# DSPCONN2.net
KiCad netlist of a schematic drawn in Altium Designer
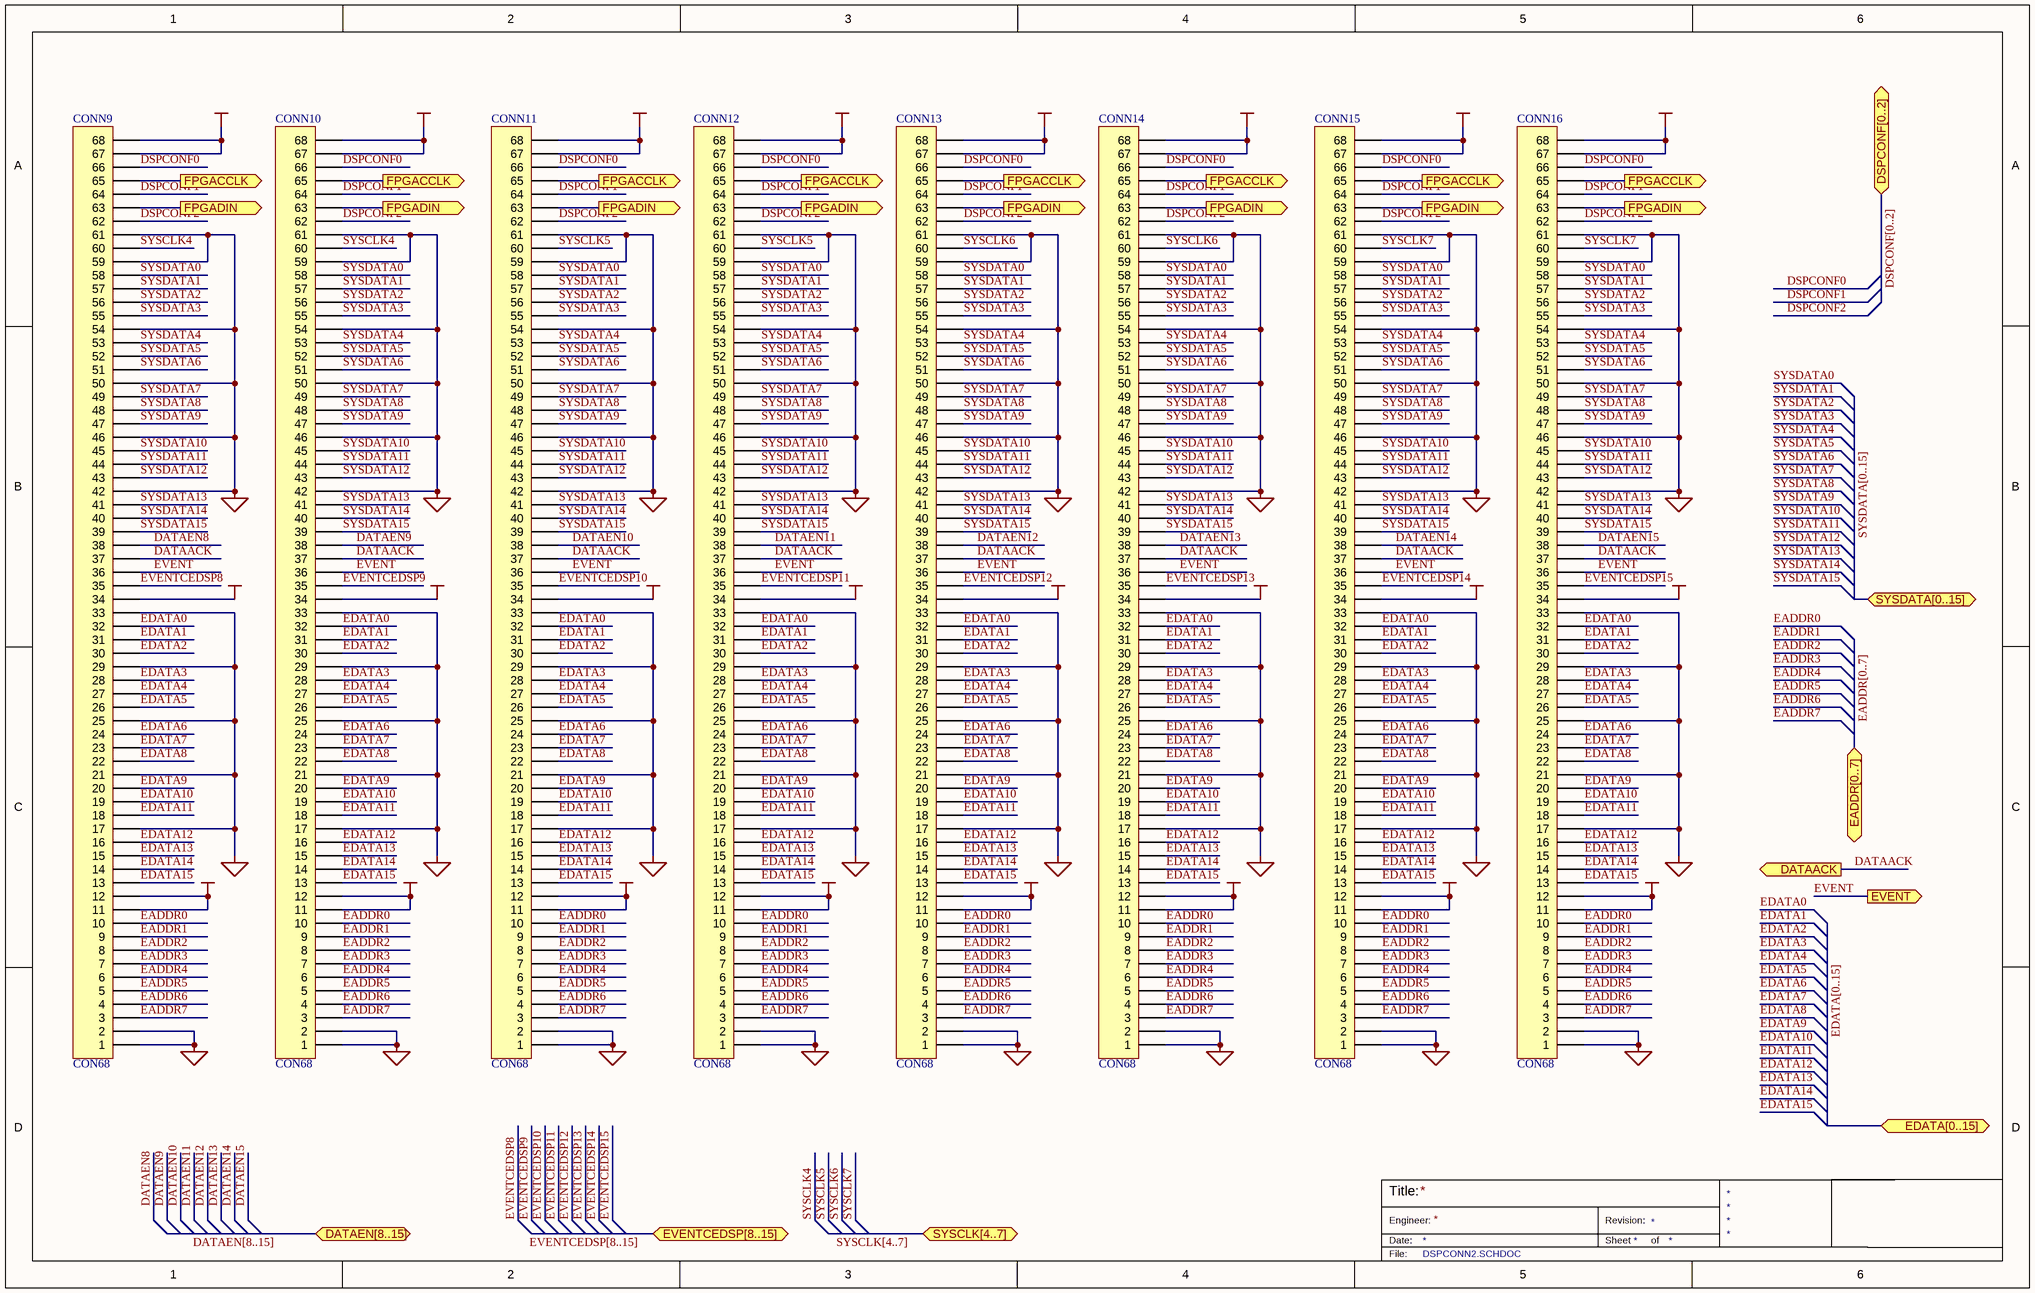
[diagram p0: DSPCONN2.SCHDOC]

(export (version "E")
  (design (tool "Eeschema 10.0.6"))
  (components
    (comp (ref "CONN9")
      (value "CON68")
      (footprint "MOLEX 15921068")
      (libsource (lib "My devices") (part "CON68"))
    )
    (comp (ref "CONN10")
      (value "CON68")
      (footprint "MOLEX 15921068")
      (libsource (lib "My devices") (part "CON68"))
    )
    (comp (ref "CONN11")
      (value "CON68")
      (footprint "MOLEX 15921068")
      (libsource (lib "My devices") (part "CON68"))
    )
    (comp (ref "CONN12")
      (value "CON68")
      (footprint "MOLEX 15921068")
      (libsource (lib "My devices") (part "CON68"))
    )
    (comp (ref "CONN13")
      (value "CON68")
      (footprint "MOLEX 15921068")
      (libsource (lib "My devices") (part "CON68"))
    )
    (comp (ref "CONN14")
      (value "CON68")
      (footprint "MOLEX 15921068")
      (libsource (lib "My devices") (part "CON68"))
    )
    (comp (ref "CONN15")
      (value "CON68")
      (footprint "MOLEX 15921068")
      (libsource (lib "My devices") (part "CON68"))
    )
    (comp (ref "CONN16")
      (value "CON68")
      (footprint "MOLEX 15921068")
      (libsource (lib "My devices") (part "CON68"))
    )
  )
  (nets
    (net (code "1") (name "+5VCC") (class "Default")
      (node (ref "CONN10") (pin "34") (pinfunction "34_34") (pintype "passive"))
      (node (ref "CONN11") (pin "34") (pinfunction "34_34") (pintype "passive"))
      (node (ref "CONN12") (pin "34") (pinfunction "34_34") (pintype "passive"))
      (node (ref "CONN13") (pin "34") (pinfunction "34_34") (pintype "passive"))
      (node (ref "CONN14") (pin "34") (pinfunction "34_34") (pintype "passive"))
      (node (ref "CONN15") (pin "34") (pinfunction "34_34") (pintype "passive"))
      (node (ref "CONN16") (pin "34") (pinfunction "34_34") (pintype "passive"))
      (node (ref "CONN9") (pin "34") (pinfunction "34_34") (pintype "passive"))
    )
    (net (code "2") (name "/DATAACK") (class "Default")
      (node (ref "CONN10") (pin "37") (pinfunction "37_37") (pintype "passive"))
      (node (ref "CONN11") (pin "37") (pinfunction "37_37") (pintype "passive"))
      (node (ref "CONN12") (pin "37") (pinfunction "37_37") (pintype "passive"))
      (node (ref "CONN13") (pin "37") (pinfunction "37_37") (pintype "passive"))
      (node (ref "CONN14") (pin "37") (pinfunction "37_37") (pintype "passive"))
      (node (ref "CONN15") (pin "37") (pinfunction "37_37") (pintype "passive"))
      (node (ref "CONN16") (pin "37") (pinfunction "37_37") (pintype "passive"))
      (node (ref "CONN9") (pin "37") (pinfunction "37_37") (pintype "passive"))
    )
    (net (code "3") (name "/DATAEN8") (class "Default")
      (node (ref "CONN9") (pin "38") (pinfunction "38_38") (pintype "passive"))
    )
    (net (code "4") (name "/DATAEN9") (class "Default")
      (node (ref "CONN10") (pin "38") (pinfunction "38_38") (pintype "passive"))
    )
    (net (code "5") (name "/DATAEN10") (class "Default")
      (node (ref "CONN11") (pin "38") (pinfunction "38_38") (pintype "passive"))
    )
    (net (code "6") (name "/DATAEN11") (class "Default")
      (node (ref "CONN12") (pin "38") (pinfunction "38_38") (pintype "passive"))
    )
    (net (code "7") (name "/DATAEN12") (class "Default")
      (node (ref "CONN13") (pin "38") (pinfunction "38_38") (pintype "passive"))
    )
    (net (code "8") (name "/DATAEN13") (class "Default")
      (node (ref "CONN14") (pin "38") (pinfunction "38_38") (pintype "passive"))
    )
    (net (code "9") (name "/DATAEN14") (class "Default")
      (node (ref "CONN15") (pin "38") (pinfunction "38_38") (pintype "passive"))
    )
    (net (code "10") (name "/DATAEN15") (class "Default")
      (node (ref "CONN16") (pin "38") (pinfunction "38_38") (pintype "passive"))
    )
    (net (code "12") (name "/DSPCONF0") (class "Default")
      (node (ref "CONN10") (pin "66") (pinfunction "66_66") (pintype "passive"))
      (node (ref "CONN11") (pin "66") (pinfunction "66_66") (pintype "passive"))
      (node (ref "CONN12") (pin "66") (pinfunction "66_66") (pintype "passive"))
      (node (ref "CONN13") (pin "66") (pinfunction "66_66") (pintype "passive"))
      (node (ref "CONN14") (pin "66") (pinfunction "66_66") (pintype "passive"))
      (node (ref "CONN15") (pin "66") (pinfunction "66_66") (pintype "passive"))
      (node (ref "CONN16") (pin "66") (pinfunction "66_66") (pintype "passive"))
      (node (ref "CONN9") (pin "66") (pinfunction "66_66") (pintype "passive"))
    )
    (net (code "13") (name "/DSPCONF1") (class "Default")
      (node (ref "CONN10") (pin "64") (pinfunction "64_64") (pintype "passive"))
      (node (ref "CONN11") (pin "64") (pinfunction "64_64") (pintype "passive"))
      (node (ref "CONN12") (pin "64") (pinfunction "64_64") (pintype "passive"))
      (node (ref "CONN13") (pin "64") (pinfunction "64_64") (pintype "passive"))
      (node (ref "CONN14") (pin "64") (pinfunction "64_64") (pintype "passive"))
      (node (ref "CONN15") (pin "64") (pinfunction "64_64") (pintype "passive"))
      (node (ref "CONN16") (pin "64") (pinfunction "64_64") (pintype "passive"))
      (node (ref "CONN9") (pin "64") (pinfunction "64_64") (pintype "passive"))
    )
    (net (code "14") (name "/DSPCONF2") (class "Default")
      (node (ref "CONN10") (pin "62") (pinfunction "62_62") (pintype "passive"))
      (node (ref "CONN11") (pin "62") (pinfunction "62_62") (pintype "passive"))
      (node (ref "CONN12") (pin "62") (pinfunction "62_62") (pintype "passive"))
      (node (ref "CONN13") (pin "62") (pinfunction "62_62") (pintype "passive"))
      (node (ref "CONN14") (pin "62") (pinfunction "62_62") (pintype "passive"))
      (node (ref "CONN15") (pin "62") (pinfunction "62_62") (pintype "passive"))
      (node (ref "CONN16") (pin "62") (pinfunction "62_62") (pintype "passive"))
      (node (ref "CONN9") (pin "62") (pinfunction "62_62") (pintype "passive"))
    )
    (net (code "16") (name "/EADDR0") (class "Default")
      (node (ref "CONN10") (pin "10") (pinfunction "10_10") (pintype "passive"))
      (node (ref "CONN11") (pin "10") (pinfunction "10_10") (pintype "passive"))
      (node (ref "CONN12") (pin "10") (pinfunction "10_10") (pintype "passive"))
      (node (ref "CONN13") (pin "10") (pinfunction "10_10") (pintype "passive"))
      (node (ref "CONN14") (pin "10") (pinfunction "10_10") (pintype "passive"))
      (node (ref "CONN15") (pin "10") (pinfunction "10_10") (pintype "passive"))
      (node (ref "CONN16") (pin "10") (pinfunction "10_10") (pintype "passive"))
      (node (ref "CONN9") (pin "10") (pinfunction "10_10") (pintype "passive"))
    )
    (net (code "17") (name "/EADDR1") (class "Default")
      (node (ref "CONN10") (pin "9") (pinfunction "9_9") (pintype "passive"))
      (node (ref "CONN11") (pin "9") (pinfunction "9_9") (pintype "passive"))
      (node (ref "CONN12") (pin "9") (pinfunction "9_9") (pintype "passive"))
      (node (ref "CONN13") (pin "9") (pinfunction "9_9") (pintype "passive"))
      (node (ref "CONN14") (pin "9") (pinfunction "9_9") (pintype "passive"))
      (node (ref "CONN15") (pin "9") (pinfunction "9_9") (pintype "passive"))
      (node (ref "CONN16") (pin "9") (pinfunction "9_9") (pintype "passive"))
      (node (ref "CONN9") (pin "9") (pinfunction "9_9") (pintype "passive"))
    )
    (net (code "18") (name "/EADDR2") (class "Default")
      (node (ref "CONN10") (pin "8") (pinfunction "8_8") (pintype "passive"))
      (node (ref "CONN11") (pin "8") (pinfunction "8_8") (pintype "passive"))
      (node (ref "CONN12") (pin "8") (pinfunction "8_8") (pintype "passive"))
      (node (ref "CONN13") (pin "8") (pinfunction "8_8") (pintype "passive"))
      (node (ref "CONN14") (pin "8") (pinfunction "8_8") (pintype "passive"))
      (node (ref "CONN15") (pin "8") (pinfunction "8_8") (pintype "passive"))
      (node (ref "CONN16") (pin "8") (pinfunction "8_8") (pintype "passive"))
      (node (ref "CONN9") (pin "8") (pinfunction "8_8") (pintype "passive"))
    )
    (net (code "19") (name "/EADDR3") (class "Default")
      (node (ref "CONN10") (pin "7") (pinfunction "7_7") (pintype "passive"))
      (node (ref "CONN11") (pin "7") (pinfunction "7_7") (pintype "passive"))
      (node (ref "CONN12") (pin "7") (pinfunction "7_7") (pintype "passive"))
      (node (ref "CONN13") (pin "7") (pinfunction "7_7") (pintype "passive"))
      (node (ref "CONN14") (pin "7") (pinfunction "7_7") (pintype "passive"))
      (node (ref "CONN15") (pin "7") (pinfunction "7_7") (pintype "passive"))
      (node (ref "CONN16") (pin "7") (pinfunction "7_7") (pintype "passive"))
      (node (ref "CONN9") (pin "7") (pinfunction "7_7") (pintype "passive"))
    )
    (net (code "20") (name "/EADDR4") (class "Default")
      (node (ref "CONN10") (pin "6") (pinfunction "6_6") (pintype "passive"))
      (node (ref "CONN11") (pin "6") (pinfunction "6_6") (pintype "passive"))
      (node (ref "CONN12") (pin "6") (pinfunction "6_6") (pintype "passive"))
      (node (ref "CONN13") (pin "6") (pinfunction "6_6") (pintype "passive"))
      (node (ref "CONN14") (pin "6") (pinfunction "6_6") (pintype "passive"))
      (node (ref "CONN15") (pin "6") (pinfunction "6_6") (pintype "passive"))
      (node (ref "CONN16") (pin "6") (pinfunction "6_6") (pintype "passive"))
      (node (ref "CONN9") (pin "6") (pinfunction "6_6") (pintype "passive"))
    )
    (net (code "21") (name "/EADDR5") (class "Default")
      (node (ref "CONN10") (pin "5") (pinfunction "5_5") (pintype "passive"))
      (node (ref "CONN11") (pin "5") (pinfunction "5_5") (pintype "passive"))
      (node (ref "CONN12") (pin "5") (pinfunction "5_5") (pintype "passive"))
      (node (ref "CONN13") (pin "5") (pinfunction "5_5") (pintype "passive"))
      (node (ref "CONN14") (pin "5") (pinfunction "5_5") (pintype "passive"))
      (node (ref "CONN15") (pin "5") (pinfunction "5_5") (pintype "passive"))
      (node (ref "CONN16") (pin "5") (pinfunction "5_5") (pintype "passive"))
      (node (ref "CONN9") (pin "5") (pinfunction "5_5") (pintype "passive"))
    )
    (net (code "22") (name "/EADDR6") (class "Default")
      (node (ref "CONN10") (pin "4") (pinfunction "4_4") (pintype "passive"))
      (node (ref "CONN11") (pin "4") (pinfunction "4_4") (pintype "passive"))
      (node (ref "CONN12") (pin "4") (pinfunction "4_4") (pintype "passive"))
      (node (ref "CONN13") (pin "4") (pinfunction "4_4") (pintype "passive"))
      (node (ref "CONN14") (pin "4") (pinfunction "4_4") (pintype "passive"))
      (node (ref "CONN15") (pin "4") (pinfunction "4_4") (pintype "passive"))
      (node (ref "CONN16") (pin "4") (pinfunction "4_4") (pintype "passive"))
      (node (ref "CONN9") (pin "4") (pinfunction "4_4") (pintype "passive"))
    )
    (net (code "23") (name "/EADDR7") (class "Default")
      (node (ref "CONN10") (pin "3") (pinfunction "3_3") (pintype "passive"))
      (node (ref "CONN11") (pin "3") (pinfunction "3_3") (pintype "passive"))
      (node (ref "CONN12") (pin "3") (pinfunction "3_3") (pintype "passive"))
      (node (ref "CONN13") (pin "3") (pinfunction "3_3") (pintype "passive"))
      (node (ref "CONN14") (pin "3") (pinfunction "3_3") (pintype "passive"))
      (node (ref "CONN15") (pin "3") (pinfunction "3_3") (pintype "passive"))
      (node (ref "CONN16") (pin "3") (pinfunction "3_3") (pintype "passive"))
      (node (ref "CONN9") (pin "3") (pinfunction "3_3") (pintype "passive"))
    )
    (net (code "25") (name "/EDATA0") (class "Default")
      (node (ref "CONN10") (pin "32") (pinfunction "32_32") (pintype "passive"))
      (node (ref "CONN11") (pin "32") (pinfunction "32_32") (pintype "passive"))
      (node (ref "CONN12") (pin "32") (pinfunction "32_32") (pintype "passive"))
      (node (ref "CONN13") (pin "32") (pinfunction "32_32") (pintype "passive"))
      (node (ref "CONN14") (pin "32") (pinfunction "32_32") (pintype "passive"))
      (node (ref "CONN15") (pin "32") (pinfunction "32_32") (pintype "passive"))
      (node (ref "CONN16") (pin "32") (pinfunction "32_32") (pintype "passive"))
      (node (ref "CONN9") (pin "32") (pinfunction "32_32") (pintype "passive"))
    )
    (net (code "26") (name "/EDATA1") (class "Default")
      (node (ref "CONN10") (pin "31") (pinfunction "31_31") (pintype "passive"))
      (node (ref "CONN11") (pin "31") (pinfunction "31_31") (pintype "passive"))
      (node (ref "CONN12") (pin "31") (pinfunction "31_31") (pintype "passive"))
      (node (ref "CONN13") (pin "31") (pinfunction "31_31") (pintype "passive"))
      (node (ref "CONN14") (pin "31") (pinfunction "31_31") (pintype "passive"))
      (node (ref "CONN15") (pin "31") (pinfunction "31_31") (pintype "passive"))
      (node (ref "CONN16") (pin "31") (pinfunction "31_31") (pintype "passive"))
      (node (ref "CONN9") (pin "31") (pinfunction "31_31") (pintype "passive"))
    )
    (net (code "27") (name "/EDATA2") (class "Default")
      (node (ref "CONN10") (pin "30") (pinfunction "30_30") (pintype "passive"))
      (node (ref "CONN11") (pin "30") (pinfunction "30_30") (pintype "passive"))
      (node (ref "CONN12") (pin "30") (pinfunction "30_30") (pintype "passive"))
      (node (ref "CONN13") (pin "30") (pinfunction "30_30") (pintype "passive"))
      (node (ref "CONN14") (pin "30") (pinfunction "30_30") (pintype "passive"))
      (node (ref "CONN15") (pin "30") (pinfunction "30_30") (pintype "passive"))
      (node (ref "CONN16") (pin "30") (pinfunction "30_30") (pintype "passive"))
      (node (ref "CONN9") (pin "30") (pinfunction "30_30") (pintype "passive"))
    )
    (net (code "28") (name "/EDATA3") (class "Default")
      (node (ref "CONN10") (pin "28") (pinfunction "28_28") (pintype "passive"))
      (node (ref "CONN11") (pin "28") (pinfunction "28_28") (pintype "passive"))
      (node (ref "CONN12") (pin "28") (pinfunction "28_28") (pintype "passive"))
      (node (ref "CONN13") (pin "28") (pinfunction "28_28") (pintype "passive"))
      (node (ref "CONN14") (pin "28") (pinfunction "28_28") (pintype "passive"))
      (node (ref "CONN15") (pin "28") (pinfunction "28_28") (pintype "passive"))
      (node (ref "CONN16") (pin "28") (pinfunction "28_28") (pintype "passive"))
      (node (ref "CONN9") (pin "28") (pinfunction "28_28") (pintype "passive"))
    )
    (net (code "29") (name "/EDATA4") (class "Default")
      (node (ref "CONN10") (pin "27") (pinfunction "27_27") (pintype "passive"))
      (node (ref "CONN11") (pin "27") (pinfunction "27_27") (pintype "passive"))
      (node (ref "CONN12") (pin "27") (pinfunction "27_27") (pintype "passive"))
      (node (ref "CONN13") (pin "27") (pinfunction "27_27") (pintype "passive"))
      (node (ref "CONN14") (pin "27") (pinfunction "27_27") (pintype "passive"))
      (node (ref "CONN15") (pin "27") (pinfunction "27_27") (pintype "passive"))
      (node (ref "CONN16") (pin "27") (pinfunction "27_27") (pintype "passive"))
      (node (ref "CONN9") (pin "27") (pinfunction "27_27") (pintype "passive"))
    )
    (net (code "30") (name "/EDATA5") (class "Default")
      (node (ref "CONN10") (pin "26") (pinfunction "26_26") (pintype "passive"))
      (node (ref "CONN11") (pin "26") (pinfunction "26_26") (pintype "passive"))
      (node (ref "CONN12") (pin "26") (pinfunction "26_26") (pintype "passive"))
      (node (ref "CONN13") (pin "26") (pinfunction "26_26") (pintype "passive"))
      (node (ref "CONN14") (pin "26") (pinfunction "26_26") (pintype "passive"))
      (node (ref "CONN15") (pin "26") (pinfunction "26_26") (pintype "passive"))
      (node (ref "CONN16") (pin "26") (pinfunction "26_26") (pintype "passive"))
      (node (ref "CONN9") (pin "26") (pinfunction "26_26") (pintype "passive"))
    )
    (net (code "31") (name "/EDATA6") (class "Default")
      (node (ref "CONN10") (pin "24") (pinfunction "24_24") (pintype "passive"))
      (node (ref "CONN11") (pin "24") (pinfunction "24_24") (pintype "passive"))
      (node (ref "CONN12") (pin "24") (pinfunction "24_24") (pintype "passive"))
      (node (ref "CONN13") (pin "24") (pinfunction "24_24") (pintype "passive"))
      (node (ref "CONN14") (pin "24") (pinfunction "24_24") (pintype "passive"))
      (node (ref "CONN15") (pin "24") (pinfunction "24_24") (pintype "passive"))
      (node (ref "CONN16") (pin "24") (pinfunction "24_24") (pintype "passive"))
      (node (ref "CONN9") (pin "24") (pinfunction "24_24") (pintype "passive"))
    )
    (net (code "32") (name "/EDATA7") (class "Default")
      (node (ref "CONN10") (pin "23") (pinfunction "23_23") (pintype "passive"))
      (node (ref "CONN11") (pin "23") (pinfunction "23_23") (pintype "passive"))
      (node (ref "CONN12") (pin "23") (pinfunction "23_23") (pintype "passive"))
      (node (ref "CONN13") (pin "23") (pinfunction "23_23") (pintype "passive"))
      (node (ref "CONN14") (pin "23") (pinfunction "23_23") (pintype "passive"))
      (node (ref "CONN15") (pin "23") (pinfunction "23_23") (pintype "passive"))
      (node (ref "CONN16") (pin "23") (pinfunction "23_23") (pintype "passive"))
      (node (ref "CONN9") (pin "23") (pinfunction "23_23") (pintype "passive"))
    )
    (net (code "33") (name "/EDATA8") (class "Default")
      (node (ref "CONN10") (pin "22") (pinfunction "22_22") (pintype "passive"))
      (node (ref "CONN11") (pin "22") (pinfunction "22_22") (pintype "passive"))
      (node (ref "CONN12") (pin "22") (pinfunction "22_22") (pintype "passive"))
      (node (ref "CONN13") (pin "22") (pinfunction "22_22") (pintype "passive"))
      (node (ref "CONN14") (pin "22") (pinfunction "22_22") (pintype "passive"))
      (node (ref "CONN15") (pin "22") (pinfunction "22_22") (pintype "passive"))
      (node (ref "CONN16") (pin "22") (pinfunction "22_22") (pintype "passive"))
      (node (ref "CONN9") (pin "22") (pinfunction "22_22") (pintype "passive"))
    )
    (net (code "34") (name "/EDATA9") (class "Default")
      (node (ref "CONN10") (pin "20") (pinfunction "20_20") (pintype "passive"))
      (node (ref "CONN11") (pin "20") (pinfunction "20_20") (pintype "passive"))
      (node (ref "CONN12") (pin "20") (pinfunction "20_20") (pintype "passive"))
      (node (ref "CONN13") (pin "20") (pinfunction "20_20") (pintype "passive"))
      (node (ref "CONN14") (pin "20") (pinfunction "20_20") (pintype "passive"))
      (node (ref "CONN15") (pin "20") (pinfunction "20_20") (pintype "passive"))
      (node (ref "CONN16") (pin "20") (pinfunction "20_20") (pintype "passive"))
      (node (ref "CONN9") (pin "20") (pinfunction "20_20") (pintype "passive"))
    )
    (net (code "35") (name "/EDATA10") (class "Default")
      (node (ref "CONN10") (pin "19") (pinfunction "19_19") (pintype "passive"))
      (node (ref "CONN11") (pin "19") (pinfunction "19_19") (pintype "passive"))
      (node (ref "CONN12") (pin "19") (pinfunction "19_19") (pintype "passive"))
      (node (ref "CONN13") (pin "19") (pinfunction "19_19") (pintype "passive"))
      (node (ref "CONN14") (pin "19") (pinfunction "19_19") (pintype "passive"))
      (node (ref "CONN15") (pin "19") (pinfunction "19_19") (pintype "passive"))
      (node (ref "CONN16") (pin "19") (pinfunction "19_19") (pintype "passive"))
      (node (ref "CONN9") (pin "19") (pinfunction "19_19") (pintype "passive"))
    )
    (net (code "36") (name "/EDATA11") (class "Default")
      (node (ref "CONN10") (pin "18") (pinfunction "18_18") (pintype "passive"))
      (node (ref "CONN11") (pin "18") (pinfunction "18_18") (pintype "passive"))
      (node (ref "CONN12") (pin "18") (pinfunction "18_18") (pintype "passive"))
      (node (ref "CONN13") (pin "18") (pinfunction "18_18") (pintype "passive"))
      (node (ref "CONN14") (pin "18") (pinfunction "18_18") (pintype "passive"))
      (node (ref "CONN15") (pin "18") (pinfunction "18_18") (pintype "passive"))
      (node (ref "CONN16") (pin "18") (pinfunction "18_18") (pintype "passive"))
      (node (ref "CONN9") (pin "18") (pinfunction "18_18") (pintype "passive"))
    )
    (net (code "37") (name "/EDATA12") (class "Default")
      (node (ref "CONN10") (pin "16") (pinfunction "16_16") (pintype "passive"))
      (node (ref "CONN11") (pin "16") (pinfunction "16_16") (pintype "passive"))
      (node (ref "CONN12") (pin "16") (pinfunction "16_16") (pintype "passive"))
      (node (ref "CONN13") (pin "16") (pinfunction "16_16") (pintype "passive"))
      (node (ref "CONN14") (pin "16") (pinfunction "16_16") (pintype "passive"))
      (node (ref "CONN15") (pin "16") (pinfunction "16_16") (pintype "passive"))
      (node (ref "CONN16") (pin "16") (pinfunction "16_16") (pintype "passive"))
      (node (ref "CONN9") (pin "16") (pinfunction "16_16") (pintype "passive"))
    )
    (net (code "38") (name "/EDATA13") (class "Default")
      (node (ref "CONN10") (pin "15") (pinfunction "15_15") (pintype "passive"))
      (node (ref "CONN11") (pin "15") (pinfunction "15_15") (pintype "passive"))
      (node (ref "CONN12") (pin "15") (pinfunction "15_15") (pintype "passive"))
      (node (ref "CONN13") (pin "15") (pinfunction "15_15") (pintype "passive"))
      (node (ref "CONN14") (pin "15") (pinfunction "15_15") (pintype "passive"))
      (node (ref "CONN15") (pin "15") (pinfunction "15_15") (pintype "passive"))
      (node (ref "CONN16") (pin "15") (pinfunction "15_15") (pintype "passive"))
      (node (ref "CONN9") (pin "15") (pinfunction "15_15") (pintype "passive"))
    )
    (net (code "39") (name "/EDATA14") (class "Default")
      (node (ref "CONN10") (pin "14") (pinfunction "14_14") (pintype "passive"))
      (node (ref "CONN11") (pin "14") (pinfunction "14_14") (pintype "passive"))
      (node (ref "CONN12") (pin "14") (pinfunction "14_14") (pintype "passive"))
      (node (ref "CONN13") (pin "14") (pinfunction "14_14") (pintype "passive"))
      (node (ref "CONN14") (pin "14") (pinfunction "14_14") (pintype "passive"))
      (node (ref "CONN15") (pin "14") (pinfunction "14_14") (pintype "passive"))
      (node (ref "CONN16") (pin "14") (pinfunction "14_14") (pintype "passive"))
      (node (ref "CONN9") (pin "14") (pinfunction "14_14") (pintype "passive"))
    )
    (net (code "40") (name "/EDATA15") (class "Default")
      (node (ref "CONN10") (pin "13") (pinfunction "13_13") (pintype "passive"))
      (node (ref "CONN11") (pin "13") (pinfunction "13_13") (pintype "passive"))
      (node (ref "CONN12") (pin "13") (pinfunction "13_13") (pintype "passive"))
      (node (ref "CONN13") (pin "13") (pinfunction "13_13") (pintype "passive"))
      (node (ref "CONN14") (pin "13") (pinfunction "13_13") (pintype "passive"))
      (node (ref "CONN15") (pin "13") (pinfunction "13_13") (pintype "passive"))
      (node (ref "CONN16") (pin "13") (pinfunction "13_13") (pintype "passive"))
      (node (ref "CONN9") (pin "13") (pinfunction "13_13") (pintype "passive"))
    )
    (net (code "42") (name "/EVENT") (class "Default")
      (node (ref "CONN10") (pin "36") (pinfunction "36_36") (pintype "passive"))
      (node (ref "CONN11") (pin "36") (pinfunction "36_36") (pintype "passive"))
      (node (ref "CONN12") (pin "36") (pinfunction "36_36") (pintype "passive"))
      (node (ref "CONN13") (pin "36") (pinfunction "36_36") (pintype "passive"))
      (node (ref "CONN14") (pin "36") (pinfunction "36_36") (pintype "passive"))
      (node (ref "CONN15") (pin "36") (pinfunction "36_36") (pintype "passive"))
      (node (ref "CONN16") (pin "36") (pinfunction "36_36") (pintype "passive"))
      (node (ref "CONN9") (pin "36") (pinfunction "36_36") (pintype "passive"))
    )
    (net (code "43") (name "/EVENTCEDSP8") (class "Default")
      (node (ref "CONN9") (pin "35") (pinfunction "35_35") (pintype "passive"))
    )
    (net (code "44") (name "/EVENTCEDSP9") (class "Default")
      (node (ref "CONN10") (pin "35") (pinfunction "35_35") (pintype "passive"))
    )
    (net (code "45") (name "/EVENTCEDSP10") (class "Default")
      (node (ref "CONN11") (pin "35") (pinfunction "35_35") (pintype "passive"))
    )
    (net (code "46") (name "/EVENTCEDSP11") (class "Default")
      (node (ref "CONN12") (pin "35") (pinfunction "35_35") (pintype "passive"))
    )
    (net (code "47") (name "/EVENTCEDSP12") (class "Default")
      (node (ref "CONN13") (pin "35") (pinfunction "35_35") (pintype "passive"))
    )
    (net (code "48") (name "/EVENTCEDSP13") (class "Default")
      (node (ref "CONN14") (pin "35") (pinfunction "35_35") (pintype "passive"))
    )
    (net (code "49") (name "/EVENTCEDSP14") (class "Default")
      (node (ref "CONN15") (pin "35") (pinfunction "35_35") (pintype "passive"))
    )
    (net (code "50") (name "/EVENTCEDSP15") (class "Default")
      (node (ref "CONN16") (pin "35") (pinfunction "35_35") (pintype "passive"))
    )
    (net (code "52") (name "/FPGACCLK") (class "Default")
      (node (ref "CONN10") (pin "65") (pinfunction "65_65") (pintype "passive"))
      (node (ref "CONN11") (pin "65") (pinfunction "65_65") (pintype "passive"))
      (node (ref "CONN12") (pin "65") (pinfunction "65_65") (pintype "passive"))
      (node (ref "CONN13") (pin "65") (pinfunction "65_65") (pintype "passive"))
      (node (ref "CONN14") (pin "65") (pinfunction "65_65") (pintype "passive"))
      (node (ref "CONN15") (pin "65") (pinfunction "65_65") (pintype "passive"))
      (node (ref "CONN16") (pin "65") (pinfunction "65_65") (pintype "passive"))
      (node (ref "CONN9") (pin "65") (pinfunction "65_65") (pintype "passive"))
    )
    (net (code "53") (name "/FPGADIN") (class "Default")
      (node (ref "CONN10") (pin "63") (pinfunction "63_63") (pintype "passive"))
      (node (ref "CONN11") (pin "63") (pinfunction "63_63") (pintype "passive"))
      (node (ref "CONN12") (pin "63") (pinfunction "63_63") (pintype "passive"))
      (node (ref "CONN13") (pin "63") (pinfunction "63_63") (pintype "passive"))
      (node (ref "CONN14") (pin "63") (pinfunction "63_63") (pintype "passive"))
      (node (ref "CONN15") (pin "63") (pinfunction "63_63") (pintype "passive"))
      (node (ref "CONN16") (pin "63") (pinfunction "63_63") (pintype "passive"))
      (node (ref "CONN9") (pin "63") (pinfunction "63_63") (pintype "passive"))
    )
    (net (code "54") (name "/SYSCLK4") (class "Default")
      (node (ref "CONN10") (pin "60") (pinfunction "60_60") (pintype "passive"))
      (node (ref "CONN9") (pin "60") (pinfunction "60_60") (pintype "passive"))
    )
    (net (code "55") (name "/SYSCLK5") (class "Default")
      (node (ref "CONN11") (pin "60") (pinfunction "60_60") (pintype "passive"))
      (node (ref "CONN12") (pin "60") (pinfunction "60_60") (pintype "passive"))
    )
    (net (code "56") (name "/SYSCLK6") (class "Default")
      (node (ref "CONN13") (pin "60") (pinfunction "60_60") (pintype "passive"))
      (node (ref "CONN14") (pin "60") (pinfunction "60_60") (pintype "passive"))
    )
    (net (code "57") (name "/SYSCLK7") (class "Default")
      (node (ref "CONN15") (pin "60") (pinfunction "60_60") (pintype "passive"))
      (node (ref "CONN16") (pin "60") (pinfunction "60_60") (pintype "passive"))
    )
    (net (code "59") (name "/SYSDATA0") (class "Default")
      (node (ref "CONN10") (pin "58") (pinfunction "58_58") (pintype "passive"))
      (node (ref "CONN11") (pin "58") (pinfunction "58_58") (pintype "passive"))
      (node (ref "CONN12") (pin "58") (pinfunction "58_58") (pintype "passive"))
      (node (ref "CONN13") (pin "58") (pinfunction "58_58") (pintype "passive"))
      (node (ref "CONN14") (pin "58") (pinfunction "58_58") (pintype "passive"))
      (node (ref "CONN15") (pin "58") (pinfunction "58_58") (pintype "passive"))
      (node (ref "CONN16") (pin "58") (pinfunction "58_58") (pintype "passive"))
      (node (ref "CONN9") (pin "58") (pinfunction "58_58") (pintype "passive"))
    )
    (net (code "60") (name "/SYSDATA1") (class "Default")
      (node (ref "CONN10") (pin "57") (pinfunction "57_57") (pintype "passive"))
      (node (ref "CONN11") (pin "57") (pinfunction "57_57") (pintype "passive"))
      (node (ref "CONN12") (pin "57") (pinfunction "57_57") (pintype "passive"))
      (node (ref "CONN13") (pin "57") (pinfunction "57_57") (pintype "passive"))
      (node (ref "CONN14") (pin "57") (pinfunction "57_57") (pintype "passive"))
      (node (ref "CONN15") (pin "57") (pinfunction "57_57") (pintype "passive"))
      (node (ref "CONN16") (pin "57") (pinfunction "57_57") (pintype "passive"))
      (node (ref "CONN9") (pin "57") (pinfunction "57_57") (pintype "passive"))
    )
    (net (code "61") (name "/SYSDATA2") (class "Default")
      (node (ref "CONN10") (pin "56") (pinfunction "56_56") (pintype "passive"))
      (node (ref "CONN11") (pin "56") (pinfunction "56_56") (pintype "passive"))
      (node (ref "CONN12") (pin "56") (pinfunction "56_56") (pintype "passive"))
      (node (ref "CONN13") (pin "56") (pinfunction "56_56") (pintype "passive"))
      (node (ref "CONN14") (pin "56") (pinfunction "56_56") (pintype "passive"))
      (node (ref "CONN15") (pin "56") (pinfunction "56_56") (pintype "passive"))
      (node (ref "CONN16") (pin "56") (pinfunction "56_56") (pintype "passive"))
      (node (ref "CONN9") (pin "56") (pinfunction "56_56") (pintype "passive"))
    )
    (net (code "62") (name "/SYSDATA3") (class "Default")
      (node (ref "CONN10") (pin "55") (pinfunction "55_55") (pintype "passive"))
      (node (ref "CONN11") (pin "55") (pinfunction "55_55") (pintype "passive"))
      (node (ref "CONN12") (pin "55") (pinfunction "55_55") (pintype "passive"))
      (node (ref "CONN13") (pin "55") (pinfunction "55_55") (pintype "passive"))
      (node (ref "CONN14") (pin "55") (pinfunction "55_55") (pintype "passive"))
      (node (ref "CONN15") (pin "55") (pinfunction "55_55") (pintype "passive"))
      (node (ref "CONN16") (pin "55") (pinfunction "55_55") (pintype "passive"))
      (node (ref "CONN9") (pin "55") (pinfunction "55_55") (pintype "passive"))
    )
    (net (code "63") (name "/SYSDATA4") (class "Default")
      (node (ref "CONN10") (pin "53") (pinfunction "53_53") (pintype "passive"))
      (node (ref "CONN11") (pin "53") (pinfunction "53_53") (pintype "passive"))
      (node (ref "CONN12") (pin "53") (pinfunction "53_53") (pintype "passive"))
      (node (ref "CONN13") (pin "53") (pinfunction "53_53") (pintype "passive"))
      (node (ref "CONN14") (pin "53") (pinfunction "53_53") (pintype "passive"))
      (node (ref "CONN15") (pin "53") (pinfunction "53_53") (pintype "passive"))
      (node (ref "CONN16") (pin "53") (pinfunction "53_53") (pintype "passive"))
      (node (ref "CONN9") (pin "53") (pinfunction "53_53") (pintype "passive"))
    )
    (net (code "64") (name "/SYSDATA5") (class "Default")
      (node (ref "CONN10") (pin "52") (pinfunction "52_52") (pintype "passive"))
      (node (ref "CONN11") (pin "52") (pinfunction "52_52") (pintype "passive"))
      (node (ref "CONN12") (pin "52") (pinfunction "52_52") (pintype "passive"))
      (node (ref "CONN13") (pin "52") (pinfunction "52_52") (pintype "passive"))
      (node (ref "CONN14") (pin "52") (pinfunction "52_52") (pintype "passive"))
      (node (ref "CONN15") (pin "52") (pinfunction "52_52") (pintype "passive"))
      (node (ref "CONN16") (pin "52") (pinfunction "52_52") (pintype "passive"))
      (node (ref "CONN9") (pin "52") (pinfunction "52_52") (pintype "passive"))
    )
    (net (code "65") (name "/SYSDATA6") (class "Default")
      (node (ref "CONN10") (pin "51") (pinfunction "51_51") (pintype "passive"))
      (node (ref "CONN11") (pin "51") (pinfunction "51_51") (pintype "passive"))
      (node (ref "CONN12") (pin "51") (pinfunction "51_51") (pintype "passive"))
      (node (ref "CONN13") (pin "51") (pinfunction "51_51") (pintype "passive"))
      (node (ref "CONN14") (pin "51") (pinfunction "51_51") (pintype "passive"))
      (node (ref "CONN15") (pin "51") (pinfunction "51_51") (pintype "passive"))
      (node (ref "CONN16") (pin "51") (pinfunction "51_51") (pintype "passive"))
      (node (ref "CONN9") (pin "51") (pinfunction "51_51") (pintype "passive"))
    )
    (net (code "66") (name "/SYSDATA7") (class "Default")
      (node (ref "CONN10") (pin "49") (pinfunction "49_49") (pintype "passive"))
      (node (ref "CONN11") (pin "49") (pinfunction "49_49") (pintype "passive"))
      (node (ref "CONN12") (pin "49") (pinfunction "49_49") (pintype "passive"))
      (node (ref "CONN13") (pin "49") (pinfunction "49_49") (pintype "passive"))
      (node (ref "CONN14") (pin "49") (pinfunction "49_49") (pintype "passive"))
      (node (ref "CONN15") (pin "49") (pinfunction "49_49") (pintype "passive"))
      (node (ref "CONN16") (pin "49") (pinfunction "49_49") (pintype "passive"))
      (node (ref "CONN9") (pin "49") (pinfunction "49_49") (pintype "passive"))
    )
    (net (code "67") (name "/SYSDATA8") (class "Default")
      (node (ref "CONN10") (pin "48") (pinfunction "48_48") (pintype "passive"))
      (node (ref "CONN11") (pin "48") (pinfunction "48_48") (pintype "passive"))
      (node (ref "CONN12") (pin "48") (pinfunction "48_48") (pintype "passive"))
      (node (ref "CONN13") (pin "48") (pinfunction "48_48") (pintype "passive"))
      (node (ref "CONN14") (pin "48") (pinfunction "48_48") (pintype "passive"))
      (node (ref "CONN15") (pin "48") (pinfunction "48_48") (pintype "passive"))
      (node (ref "CONN16") (pin "48") (pinfunction "48_48") (pintype "passive"))
      (node (ref "CONN9") (pin "48") (pinfunction "48_48") (pintype "passive"))
    )
    (net (code "68") (name "/SYSDATA9") (class "Default")
      (node (ref "CONN10") (pin "47") (pinfunction "47_47") (pintype "passive"))
      (node (ref "CONN11") (pin "47") (pinfunction "47_47") (pintype "passive"))
      (node (ref "CONN12") (pin "47") (pinfunction "47_47") (pintype "passive"))
      (node (ref "CONN13") (pin "47") (pinfunction "47_47") (pintype "passive"))
      (node (ref "CONN14") (pin "47") (pinfunction "47_47") (pintype "passive"))
      (node (ref "CONN15") (pin "47") (pinfunction "47_47") (pintype "passive"))
      (node (ref "CONN16") (pin "47") (pinfunction "47_47") (pintype "passive"))
      (node (ref "CONN9") (pin "47") (pinfunction "47_47") (pintype "passive"))
    )
    (net (code "69") (name "/SYSDATA10") (class "Default")
      (node (ref "CONN10") (pin "45") (pinfunction "45_45") (pintype "passive"))
      (node (ref "CONN11") (pin "45") (pinfunction "45_45") (pintype "passive"))
      (node (ref "CONN12") (pin "45") (pinfunction "45_45") (pintype "passive"))
      (node (ref "CONN13") (pin "45") (pinfunction "45_45") (pintype "passive"))
      (node (ref "CONN14") (pin "45") (pinfunction "45_45") (pintype "passive"))
      (node (ref "CONN15") (pin "45") (pinfunction "45_45") (pintype "passive"))
      (node (ref "CONN16") (pin "45") (pinfunction "45_45") (pintype "passive"))
      (node (ref "CONN9") (pin "45") (pinfunction "45_45") (pintype "passive"))
    )
    (net (code "70") (name "/SYSDATA11") (class "Default")
      (node (ref "CONN10") (pin "44") (pinfunction "44_44") (pintype "passive"))
      (node (ref "CONN11") (pin "44") (pinfunction "44_44") (pintype "passive"))
      (node (ref "CONN12") (pin "44") (pinfunction "44_44") (pintype "passive"))
      (node (ref "CONN13") (pin "44") (pinfunction "44_44") (pintype "passive"))
      (node (ref "CONN14") (pin "44") (pinfunction "44_44") (pintype "passive"))
      (node (ref "CONN15") (pin "44") (pinfunction "44_44") (pintype "passive"))
      (node (ref "CONN16") (pin "44") (pinfunction "44_44") (pintype "passive"))
      (node (ref "CONN9") (pin "44") (pinfunction "44_44") (pintype "passive"))
    )
    (net (code "71") (name "/SYSDATA12") (class "Default")
      (node (ref "CONN10") (pin "43") (pinfunction "43_43") (pintype "passive"))
      (node (ref "CONN11") (pin "43") (pinfunction "43_43") (pintype "passive"))
      (node (ref "CONN12") (pin "43") (pinfunction "43_43") (pintype "passive"))
      (node (ref "CONN13") (pin "43") (pinfunction "43_43") (pintype "passive"))
      (node (ref "CONN14") (pin "43") (pinfunction "43_43") (pintype "passive"))
      (node (ref "CONN15") (pin "43") (pinfunction "43_43") (pintype "passive"))
      (node (ref "CONN16") (pin "43") (pinfunction "43_43") (pintype "passive"))
      (node (ref "CONN9") (pin "43") (pinfunction "43_43") (pintype "passive"))
    )
    (net (code "72") (name "/SYSDATA13") (class "Default")
      (node (ref "CONN10") (pin "41") (pinfunction "41_41") (pintype "passive"))
      (node (ref "CONN11") (pin "41") (pinfunction "41_41") (pintype "passive"))
      (node (ref "CONN12") (pin "41") (pinfunction "41_41") (pintype "passive"))
      (node (ref "CONN13") (pin "41") (pinfunction "41_41") (pintype "passive"))
      (node (ref "CONN14") (pin "41") (pinfunction "41_41") (pintype "passive"))
      (node (ref "CONN15") (pin "41") (pinfunction "41_41") (pintype "passive"))
      (node (ref "CONN16") (pin "41") (pinfunction "41_41") (pintype "passive"))
      (node (ref "CONN9") (pin "41") (pinfunction "41_41") (pintype "passive"))
    )
    (net (code "73") (name "/SYSDATA14") (class "Default")
      (node (ref "CONN10") (pin "40") (pinfunction "40_40") (pintype "passive"))
      (node (ref "CONN11") (pin "40") (pinfunction "40_40") (pintype "passive"))
      (node (ref "CONN12") (pin "40") (pinfunction "40_40") (pintype "passive"))
      (node (ref "CONN13") (pin "40") (pinfunction "40_40") (pintype "passive"))
      (node (ref "CONN14") (pin "40") (pinfunction "40_40") (pintype "passive"))
      (node (ref "CONN15") (pin "40") (pinfunction "40_40") (pintype "passive"))
      (node (ref "CONN16") (pin "40") (pinfunction "40_40") (pintype "passive"))
      (node (ref "CONN9") (pin "40") (pinfunction "40_40") (pintype "passive"))
    )
    (net (code "74") (name "/SYSDATA15") (class "Default")
      (node (ref "CONN10") (pin "39") (pinfunction "39_39") (pintype "passive"))
      (node (ref "CONN11") (pin "39") (pinfunction "39_39") (pintype "passive"))
      (node (ref "CONN12") (pin "39") (pinfunction "39_39") (pintype "passive"))
      (node (ref "CONN13") (pin "39") (pinfunction "39_39") (pintype "passive"))
      (node (ref "CONN14") (pin "39") (pinfunction "39_39") (pintype "passive"))
      (node (ref "CONN15") (pin "39") (pinfunction "39_39") (pintype "passive"))
      (node (ref "CONN16") (pin "39") (pinfunction "39_39") (pintype "passive"))
      (node (ref "CONN9") (pin "39") (pinfunction "39_39") (pintype "passive"))
    )
    (net (code "76") (name "GND") (class "Default")
      (node (ref "CONN10") (pin "1") (pinfunction "1_1") (pintype "passive"))
      (node (ref "CONN10") (pin "17") (pinfunction "17_17") (pintype "passive"))
      (node (ref "CONN10") (pin "2") (pinfunction "2_2") (pintype "passive"))
      (node (ref "CONN10") (pin "21") (pinfunction "21_21") (pintype "passive"))
      (node (ref "CONN10") (pin "25") (pinfunction "25_25") (pintype "passive"))
      (node (ref "CONN10") (pin "29") (pinfunction "29_29") (pintype "passive"))
      (node (ref "CONN10") (pin "33") (pinfunction "33_33") (pintype "passive"))
      (node (ref "CONN10") (pin "42") (pinfunction "42_42") (pintype "passive"))
      (node (ref "CONN10") (pin "46") (pinfunction "46_46") (pintype "passive"))
      (node (ref "CONN10") (pin "50") (pinfunction "50_50") (pintype "passive"))
      (node (ref "CONN10") (pin "54") (pinfunction "54_54") (pintype "passive"))
      (node (ref "CONN10") (pin "59") (pinfunction "59_59") (pintype "passive"))
      (node (ref "CONN10") (pin "61") (pinfunction "61_61") (pintype "passive"))
      (node (ref "CONN11") (pin "1") (pinfunction "1_1") (pintype "passive"))
      (node (ref "CONN11") (pin "17") (pinfunction "17_17") (pintype "passive"))
      (node (ref "CONN11") (pin "2") (pinfunction "2_2") (pintype "passive"))
      (node (ref "CONN11") (pin "21") (pinfunction "21_21") (pintype "passive"))
      (node (ref "CONN11") (pin "25") (pinfunction "25_25") (pintype "passive"))
      (node (ref "CONN11") (pin "29") (pinfunction "29_29") (pintype "passive"))
      (node (ref "CONN11") (pin "33") (pinfunction "33_33") (pintype "passive"))
      (node (ref "CONN11") (pin "42") (pinfunction "42_42") (pintype "passive"))
      (node (ref "CONN11") (pin "46") (pinfunction "46_46") (pintype "passive"))
      (node (ref "CONN11") (pin "50") (pinfunction "50_50") (pintype "passive"))
      (node (ref "CONN11") (pin "54") (pinfunction "54_54") (pintype "passive"))
      (node (ref "CONN11") (pin "59") (pinfunction "59_59") (pintype "passive"))
      (node (ref "CONN11") (pin "61") (pinfunction "61_61") (pintype "passive"))
      (node (ref "CONN12") (pin "1") (pinfunction "1_1") (pintype "passive"))
      (node (ref "CONN12") (pin "17") (pinfunction "17_17") (pintype "passive"))
      (node (ref "CONN12") (pin "2") (pinfunction "2_2") (pintype "passive"))
      (node (ref "CONN12") (pin "21") (pinfunction "21_21") (pintype "passive"))
      (node (ref "CONN12") (pin "25") (pinfunction "25_25") (pintype "passive"))
      (node (ref "CONN12") (pin "29") (pinfunction "29_29") (pintype "passive"))
      (node (ref "CONN12") (pin "33") (pinfunction "33_33") (pintype "passive"))
      (node (ref "CONN12") (pin "42") (pinfunction "42_42") (pintype "passive"))
      (node (ref "CONN12") (pin "46") (pinfunction "46_46") (pintype "passive"))
      (node (ref "CONN12") (pin "50") (pinfunction "50_50") (pintype "passive"))
      (node (ref "CONN12") (pin "54") (pinfunction "54_54") (pintype "passive"))
      (node (ref "CONN12") (pin "59") (pinfunction "59_59") (pintype "passive"))
      (node (ref "CONN12") (pin "61") (pinfunction "61_61") (pintype "passive"))
      (node (ref "CONN13") (pin "1") (pinfunction "1_1") (pintype "passive"))
      (node (ref "CONN13") (pin "17") (pinfunction "17_17") (pintype "passive"))
      (node (ref "CONN13") (pin "2") (pinfunction "2_2") (pintype "passive"))
      (node (ref "CONN13") (pin "21") (pinfunction "21_21") (pintype "passive"))
      (node (ref "CONN13") (pin "25") (pinfunction "25_25") (pintype "passive"))
      (node (ref "CONN13") (pin "29") (pinfunction "29_29") (pintype "passive"))
      (node (ref "CONN13") (pin "33") (pinfunction "33_33") (pintype "passive"))
      (node (ref "CONN13") (pin "42") (pinfunction "42_42") (pintype "passive"))
      (node (ref "CONN13") (pin "46") (pinfunction "46_46") (pintype "passive"))
      (node (ref "CONN13") (pin "50") (pinfunction "50_50") (pintype "passive"))
      (node (ref "CONN13") (pin "54") (pinfunction "54_54") (pintype "passive"))
      (node (ref "CONN13") (pin "59") (pinfunction "59_59") (pintype "passive"))
      (node (ref "CONN13") (pin "61") (pinfunction "61_61") (pintype "passive"))
      (node (ref "CONN14") (pin "1") (pinfunction "1_1") (pintype "passive"))
      (node (ref "CONN14") (pin "17") (pinfunction "17_17") (pintype "passive"))
      (node (ref "CONN14") (pin "2") (pinfunction "2_2") (pintype "passive"))
      (node (ref "CONN14") (pin "21") (pinfunction "21_21") (pintype "passive"))
      (node (ref "CONN14") (pin "25") (pinfunction "25_25") (pintype "passive"))
      (node (ref "CONN14") (pin "29") (pinfunction "29_29") (pintype "passive"))
      (node (ref "CONN14") (pin "33") (pinfunction "33_33") (pintype "passive"))
      (node (ref "CONN14") (pin "42") (pinfunction "42_42") (pintype "passive"))
      (node (ref "CONN14") (pin "46") (pinfunction "46_46") (pintype "passive"))
      (node (ref "CONN14") (pin "50") (pinfunction "50_50") (pintype "passive"))
      (node (ref "CONN14") (pin "54") (pinfunction "54_54") (pintype "passive"))
      (node (ref "CONN14") (pin "59") (pinfunction "59_59") (pintype "passive"))
      (node (ref "CONN14") (pin "61") (pinfunction "61_61") (pintype "passive"))
      (node (ref "CONN15") (pin "1") (pinfunction "1_1") (pintype "passive"))
      (node (ref "CONN15") (pin "17") (pinfunction "17_17") (pintype "passive"))
      (node (ref "CONN15") (pin "2") (pinfunction "2_2") (pintype "passive"))
      (node (ref "CONN15") (pin "21") (pinfunction "21_21") (pintype "passive"))
      (node (ref "CONN15") (pin "25") (pinfunction "25_25") (pintype "passive"))
      (node (ref "CONN15") (pin "29") (pinfunction "29_29") (pintype "passive"))
      (node (ref "CONN15") (pin "33") (pinfunction "33_33") (pintype "passive"))
      (node (ref "CONN15") (pin "42") (pinfunction "42_42") (pintype "passive"))
      (node (ref "CONN15") (pin "46") (pinfunction "46_46") (pintype "passive"))
      (node (ref "CONN15") (pin "50") (pinfunction "50_50") (pintype "passive"))
      (node (ref "CONN15") (pin "54") (pinfunction "54_54") (pintype "passive"))
      (node (ref "CONN15") (pin "59") (pinfunction "59_59") (pintype "passive"))
      (node (ref "CONN15") (pin "61") (pinfunction "61_61") (pintype "passive"))
      (node (ref "CONN16") (pin "1") (pinfunction "1_1") (pintype "passive"))
      (node (ref "CONN16") (pin "17") (pinfunction "17_17") (pintype "passive"))
      (node (ref "CONN16") (pin "2") (pinfunction "2_2") (pintype "passive"))
      (node (ref "CONN16") (pin "21") (pinfunction "21_21") (pintype "passive"))
      (node (ref "CONN16") (pin "25") (pinfunction "25_25") (pintype "passive"))
      (node (ref "CONN16") (pin "29") (pinfunction "29_29") (pintype "passive"))
      (node (ref "CONN16") (pin "33") (pinfunction "33_33") (pintype "passive"))
      (node (ref "CONN16") (pin "42") (pinfunction "42_42") (pintype "passive"))
      (node (ref "CONN16") (pin "46") (pinfunction "46_46") (pintype "passive"))
      (node (ref "CONN16") (pin "50") (pinfunction "50_50") (pintype "passive"))
      (node (ref "CONN16") (pin "54") (pinfunction "54_54") (pintype "passive"))
      (node (ref "CONN16") (pin "59") (pinfunction "59_59") (pintype "passive"))
      (node (ref "CONN16") (pin "61") (pinfunction "61_61") (pintype "passive"))
      (node (ref "CONN9") (pin "1") (pinfunction "1_1") (pintype "passive"))
      (node (ref "CONN9") (pin "17") (pinfunction "17_17") (pintype "passive"))
      (node (ref "CONN9") (pin "2") (pinfunction "2_2") (pintype "passive"))
      (node (ref "CONN9") (pin "21") (pinfunction "21_21") (pintype "passive"))
      (node (ref "CONN9") (pin "25") (pinfunction "25_25") (pintype "passive"))
      (node (ref "CONN9") (pin "29") (pinfunction "29_29") (pintype "passive"))
      (node (ref "CONN9") (pin "33") (pinfunction "33_33") (pintype "passive"))
      (node (ref "CONN9") (pin "42") (pinfunction "42_42") (pintype "passive"))
      (node (ref "CONN9") (pin "46") (pinfunction "46_46") (pintype "passive"))
      (node (ref "CONN9") (pin "50") (pinfunction "50_50") (pintype "passive"))
      (node (ref "CONN9") (pin "54") (pinfunction "54_54") (pintype "passive"))
      (node (ref "CONN9") (pin "59") (pinfunction "59_59") (pintype "passive"))
      (node (ref "CONN9") (pin "61") (pinfunction "61_61") (pintype "passive"))
    )
    (net (code "77") (name "VCC2") (class "Default")
      (node (ref "CONN10") (pin "11") (pinfunction "11_11") (pintype "passive"))
      (node (ref "CONN10") (pin "12") (pinfunction "12_12") (pintype "passive"))
      (node (ref "CONN10") (pin "67") (pinfunction "67_67") (pintype "passive"))
      (node (ref "CONN10") (pin "68") (pinfunction "68_68") (pintype "passive"))
      (node (ref "CONN11") (pin "11") (pinfunction "11_11") (pintype "passive"))
      (node (ref "CONN11") (pin "12") (pinfunction "12_12") (pintype "passive"))
      (node (ref "CONN11") (pin "67") (pinfunction "67_67") (pintype "passive"))
      (node (ref "CONN11") (pin "68") (pinfunction "68_68") (pintype "passive"))
      (node (ref "CONN12") (pin "11") (pinfunction "11_11") (pintype "passive"))
      (node (ref "CONN12") (pin "12") (pinfunction "12_12") (pintype "passive"))
      (node (ref "CONN12") (pin "67") (pinfunction "67_67") (pintype "passive"))
      (node (ref "CONN12") (pin "68") (pinfunction "68_68") (pintype "passive"))
      (node (ref "CONN13") (pin "11") (pinfunction "11_11") (pintype "passive"))
      (node (ref "CONN13") (pin "12") (pinfunction "12_12") (pintype "passive"))
      (node (ref "CONN13") (pin "67") (pinfunction "67_67") (pintype "passive"))
      (node (ref "CONN13") (pin "68") (pinfunction "68_68") (pintype "passive"))
      (node (ref "CONN14") (pin "11") (pinfunction "11_11") (pintype "passive"))
      (node (ref "CONN14") (pin "12") (pinfunction "12_12") (pintype "passive"))
      (node (ref "CONN14") (pin "67") (pinfunction "67_67") (pintype "passive"))
      (node (ref "CONN14") (pin "68") (pinfunction "68_68") (pintype "passive"))
      (node (ref "CONN15") (pin "11") (pinfunction "11_11") (pintype "passive"))
      (node (ref "CONN15") (pin "12") (pinfunction "12_12") (pintype "passive"))
      (node (ref "CONN15") (pin "67") (pinfunction "67_67") (pintype "passive"))
      (node (ref "CONN15") (pin "68") (pinfunction "68_68") (pintype "passive"))
      (node (ref "CONN16") (pin "11") (pinfunction "11_11") (pintype "passive"))
      (node (ref "CONN16") (pin "12") (pinfunction "12_12") (pintype "passive"))
      (node (ref "CONN16") (pin "67") (pinfunction "67_67") (pintype "passive"))
      (node (ref "CONN16") (pin "68") (pinfunction "68_68") (pintype "passive"))
      (node (ref "CONN9") (pin "11") (pinfunction "11_11") (pintype "passive"))
      (node (ref "CONN9") (pin "12") (pinfunction "12_12") (pintype "passive"))
      (node (ref "CONN9") (pin "67") (pinfunction "67_67") (pintype "passive"))
      (node (ref "CONN9") (pin "68") (pinfunction "68_68") (pintype "passive"))
    )
  )
)
